# 1117_Adj.net
KiCad netlist of a schematic drawn in EAGLE
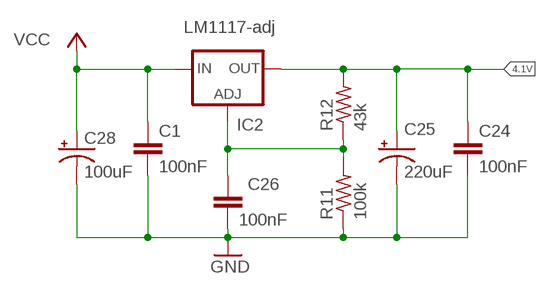
[diagram p0: schematic, sheet 1]

(export (version "E")
  (design (tool "Eeschema 10.0.6"))
  (components
    (comp (ref "C1")
      (value "100nF")
      (footprint "eagle-import:C050-024X044")
      (libsource (lib "eagle-import") (part "C-EU050-024X044"))
    )
    (comp (ref "C24")
      (value "100nF")
      (footprint "eagle-import:C050-024X044")
      (libsource (lib "eagle-import") (part "C-EU050-024X044"))
    )
    (comp (ref "C25")
      (value "220uF")
      (footprint "eagle-import:E2,5-6")
      (libsource (lib "eagle-import") (part "CPOL-USE2.5-6"))
    )
    (comp (ref "C26")
      (value "100nF")
      (footprint "eagle-import:C050-024X044")
      (libsource (lib "eagle-import") (part "C-EU050-024X044"))
    )
    (comp (ref "C28")
      (value "100uF")
      (footprint "eagle-import:E2,5-6")
      (libsource (lib "eagle-import") (part "CPOL-USE2.5-6"))
    )
    (comp (ref "IC2")
      (value "LM1117-adj")
      (footprint "eagle-import:SOT223")
      (libsource (lib "eagle-import") (part "LD117A?S25TR"))
    )
    (comp (ref "R11")
      (value "100k")
      (footprint "eagle-import:0204_7")
      (libsource (lib "eagle-import") (part "R-US_0204/7"))
    )
    (comp (ref "R12")
      (value "43k")
      (footprint "eagle-import:0204_7")
      (libsource (lib "eagle-import") (part "R-US_0204/7"))
    )
  )
  (nets
    (net (code "1") (name "4.1V") (class "Default")
      (node (ref "C24") (pin "1") (pinfunction "1_1") (pintype "passive"))
      (node (ref "C25") (pin "+") (pinfunction "+_+") (pintype "passive"))
      (node (ref "IC2") (pin "4") (pinfunction "OUT_4") (pintype "passive"))
      (node (ref "R12") (pin "2") (pinfunction "2_2") (pintype "passive"))
    )
    (net (code "2") (name "GND") (class "Default")
      (node (ref "C1") (pin "2") (pinfunction "2_2") (pintype "passive"))
      (node (ref "C24") (pin "2") (pinfunction "2_2") (pintype "passive"))
      (node (ref "C25") (pin "-") (pinfunction "-_-") (pintype "passive"))
      (node (ref "C26") (pin "2") (pinfunction "2_2") (pintype "passive"))
      (node (ref "C28") (pin "-") (pinfunction "-_-") (pintype "passive"))
      (node (ref "R11") (pin "1") (pinfunction "1_1") (pintype "passive"))
    )
    (net (code "3") (name "Net-(IC2-ADJ)") (class "Default")
      (node (ref "C26") (pin "1") (pinfunction "1_1") (pintype "passive"))
      (node (ref "IC2") (pin "1") (pinfunction "ADJ_1") (pintype "input"))
      (node (ref "R11") (pin "2") (pinfunction "2_2") (pintype "passive"))
      (node (ref "R12") (pin "1") (pinfunction "1_1") (pintype "passive"))
    )
    (net (code "4") (name "VCC") (class "Default")
      (node (ref "C1") (pin "1") (pinfunction "1_1") (pintype "passive"))
      (node (ref "C28") (pin "+") (pinfunction "+_+") (pintype "passive"))
      (node (ref "IC2") (pin "3") (pinfunction "IN_3") (pintype "input"))
    )
  )
)
